# console.net
KiCad netlist of a schematic drawn in EAGLE
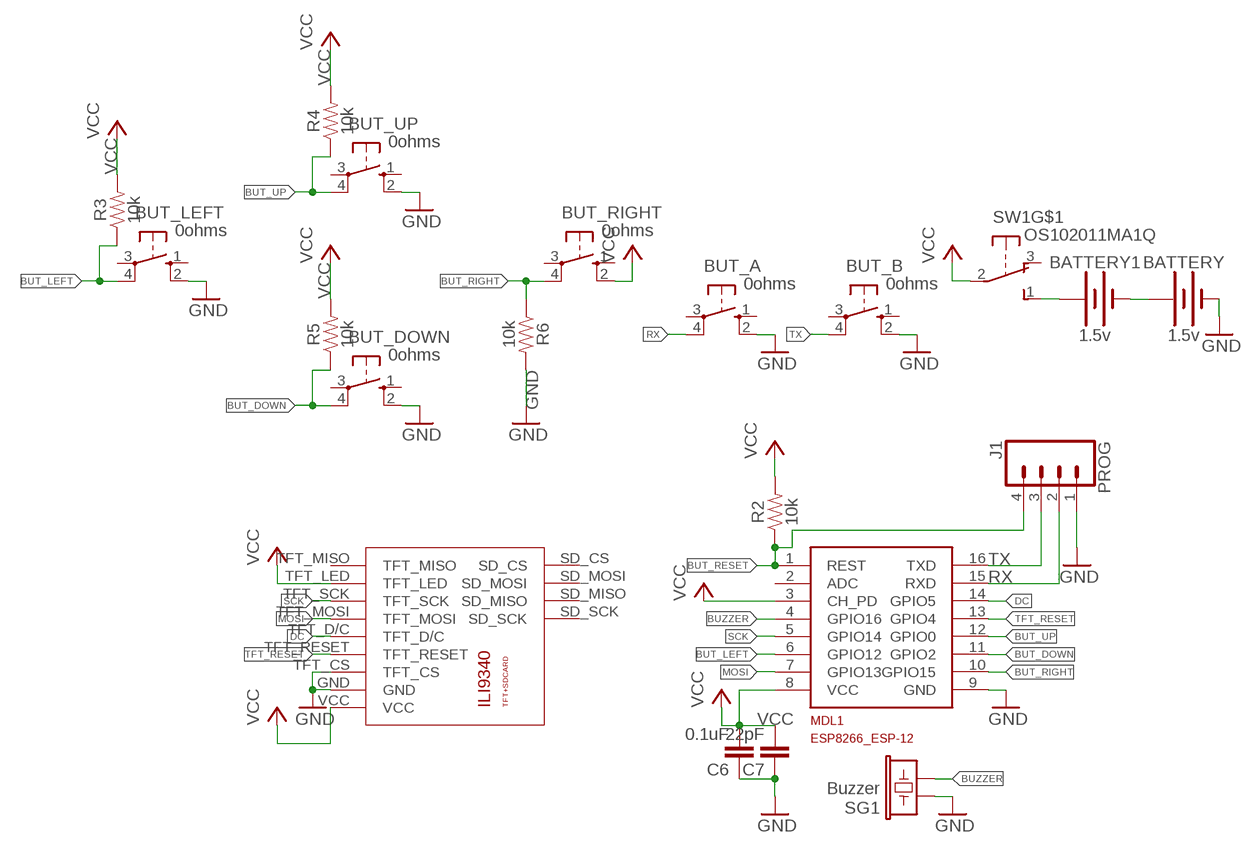
[diagram p0: schematic, sheet 1]

(export (version "E")
  (design (tool "Eeschema 10.0.6"))
  (components
    (comp (ref "BATTERY")
      (value "1.5v")
      (footprint "eagle-import:BATTERY-AA")
      (libsource (lib "eagle-import") (part "BATTERY-AA"))
    )
    (comp (ref "BATTERY1")
      (value "1.5v")
      (footprint "eagle-import:BATTERY-AA")
      (libsource (lib "eagle-import") (part "BATTERY-AA"))
    )
    (comp (ref "BUT_A")
      (value "0ohms")
      (footprint "eagle-import:B3F-10XX")
      (fields (field (name "MPN") "B3F-1000"))
      (libsource (lib "eagle-import") (part "10-XX"))
    )
    (comp (ref "BUT_B")
      (value "0ohms")
      (footprint "eagle-import:B3F-10XX")
      (fields (field (name "MPN") "B3F-1000"))
      (libsource (lib "eagle-import") (part "10-XX"))
    )
    (comp (ref "BUT_DOWN")
      (value "0ohms")
      (footprint "eagle-import:B3F-10XX")
      (fields (field (name "MPN") "B3F-1000"))
      (libsource (lib "eagle-import") (part "10-XX"))
    )
    (comp (ref "BUT_LEFT")
      (value "0ohms")
      (footprint "eagle-import:B3F-10XX")
      (fields (field (name "MPN") "B3F-1000"))
      (libsource (lib "eagle-import") (part "10-XX"))
    )
    (comp (ref "BUT_RIGHT")
      (value "0ohms")
      (footprint "eagle-import:B3F-10XX")
      (fields (field (name "MPN") "B3F-1000"))
      (libsource (lib "eagle-import") (part "10-XX"))
    )
    (comp (ref "BUT_UP")
      (value "0ohms")
      (footprint "eagle-import:B3F-10XX")
      (fields (field (name "MPN") "B3F-1000"))
      (libsource (lib "eagle-import") (part "10-XX"))
    )
    (comp (ref "C6")
      (value "0.1uF")
      (footprint "eagle-import:C0603")
      (libsource (lib "eagle-import") (part "C-EUC0603"))
    )
    (comp (ref "C7")
      (value "22pF")
      (footprint "eagle-import:C0603")
      (libsource (lib "eagle-import") (part "C-EUC0603"))
    )
    (comp (ref "J1")
      (value "PROG")
      (footprint "eagle-import:1X04_NO_SILK")
      (libsource (lib "eagle-import") (part "CONN_041X04_NO_SILK"))
    )
    (comp (ref "MDL1")
      (value "MCU")
      (footprint "eagle-import:ESP8266-ESP12")
      (libsource (lib "eagle-import") (part "ESP8266-12GPIO04/05_CORRECTED"))
    )
    (comp (ref "R2")
      (value "10k")
      (footprint "eagle-import:0603")
      (libsource (lib "eagle-import") (part "10KOHM-0603-1/10W-1%"))
    )
    (comp (ref "R3")
      (value "10k")
      (footprint "eagle-import:0603")
      (libsource (lib "eagle-import") (part "10KOHM-0603-1/10W-1%"))
    )
    (comp (ref "R4")
      (value "10k")
      (footprint "eagle-import:0603")
      (libsource (lib "eagle-import") (part "10KOHM-0603-1/10W-1%"))
    )
    (comp (ref "R5")
      (value "10k")
      (footprint "eagle-import:0603")
      (libsource (lib "eagle-import") (part "10KOHM-0603-1/10W-1%"))
    )
    (comp (ref "R6")
      (value "10k")
      (footprint "eagle-import:0603")
      (libsource (lib "eagle-import") (part "10KOHM-0603-1/10W-1%"))
    )
    (comp (ref "SG1")
      (value "Buzzer")
      (footprint "eagle-import:BUZZER-CCV")
      (libsource (lib "eagle-import") (part "BUZZERSMD2"))
    )
    (comp (ref "SW1")
      (value "OS102011MA1Q")
      (footprint "eagle-import:OS102011MA1Q")
      (libsource (lib "eagle-import") (part "OS102011MA1Q"))
    )
    (comp (ref "U$1")
      (value "ILI9340")
      (footprint "eagle-import:ILI9340")
      (libsource (lib "eagle-import") (part "ILI9340"))
    )
  )
  (nets
    (net (code "1") (name "BUT_DOWN") (class "Default")
      (node (ref "BUT_DOWN") (pin "4") (pinfunction "P1_4") (pintype "passive"))
      (node (ref "MDL1") (pin "11") (pinfunction "GPIO2_11") (pintype "bidirectional"))
      (node (ref "R5") (pin "1") (pinfunction "1_1") (pintype "passive"))
    )
    (net (code "2") (name "BUT_LEFT") (class "Default")
      (node (ref "BUT_LEFT") (pin "4") (pinfunction "P1_4") (pintype "passive"))
      (node (ref "MDL1") (pin "6") (pinfunction "GPIO12_6") (pintype "bidirectional"))
      (node (ref "R3") (pin "1") (pinfunction "1_1") (pintype "passive"))
    )
    (net (code "3") (name "BUT_RESET") (class "Default")
      (node (ref "J1") (pin "4") (pinfunction "4_4") (pintype "passive"))
      (node (ref "MDL1") (pin "1") (pinfunction "REST_1") (pintype "bidirectional"))
      (node (ref "R2") (pin "1") (pinfunction "1_1") (pintype "passive"))
    )
    (net (code "4") (name "BUT_RIGHT") (class "Default")
      (node (ref "BUT_RIGHT") (pin "4") (pinfunction "P1_4") (pintype "passive"))
      (node (ref "MDL1") (pin "10") (pinfunction "GPIO15_10") (pintype "bidirectional"))
      (node (ref "R6") (pin "1") (pinfunction "1_1") (pintype "passive"))
    )
    (net (code "5") (name "BUT_UP") (class "Default")
      (node (ref "BUT_UP") (pin "4") (pinfunction "P1_4") (pintype "passive"))
      (node (ref "MDL1") (pin "12") (pinfunction "GPIO0_12") (pintype "bidirectional"))
      (node (ref "R4") (pin "1") (pinfunction "1_1") (pintype "passive"))
    )
    (net (code "6") (name "BUZZER") (class "Default")
      (node (ref "MDL1") (pin "4") (pinfunction "GPIO16_4") (pintype "bidirectional"))
      (node (ref "SG1") (pin "-") (pinfunction "2_-") (pintype "passive"))
    )
    (net (code "7") (name "DC") (class "Default")
      (node (ref "MDL1") (pin "14") (pinfunction "GPIO5_14") (pintype "bidirectional"))
      (node (ref "U$1") (pin "TFT_D/C") (pinfunction "TFT_D/C_TFT_D/C") (pintype "input"))
    )
    (net (code "8") (name "GND") (class "Default")
      (node (ref "BATTERY") (pin "GND@1") (pinfunction "-_GND@1") (pintype "power_in"))
      (node (ref "BUT_A") (pin "2") (pinfunction "S1_2") (pintype "passive"))
      (node (ref "BUT_B") (pin "2") (pinfunction "S1_2") (pintype "passive"))
      (node (ref "BUT_DOWN") (pin "2") (pinfunction "S1_2") (pintype "passive"))
      (node (ref "BUT_LEFT") (pin "2") (pinfunction "S1_2") (pintype "passive"))
      (node (ref "BUT_UP") (pin "2") (pinfunction "S1_2") (pintype "passive"))
      (node (ref "C6") (pin "1") (pinfunction "1_1") (pintype "passive"))
      (node (ref "C7") (pin "1") (pinfunction "1_1") (pintype "passive"))
      (node (ref "J1") (pin "1") (pinfunction "1_1") (pintype "passive"))
      (node (ref "MDL1") (pin "9") (pinfunction "GND_9") (pintype "bidirectional"))
      (node (ref "R6") (pin "2") (pinfunction "2_2") (pintype "passive"))
      (node (ref "SG1") (pin "+") (pinfunction "1_+") (pintype "passive"))
      (node (ref "U$1") (pin "GND") (pinfunction "GND_GND") (pintype "power_in"))
      (node (ref "U$1") (pin "TFT_CS") (pinfunction "TFT_CS_TFT_CS") (pintype "input"))
    )
    (net (code "9") (name "MOSI") (class "Default")
      (node (ref "MDL1") (pin "7") (pinfunction "GPIO13_7") (pintype "bidirectional"))
      (node (ref "U$1") (pin "TFT_MOSI") (pinfunction "TFT_MOSI_TFT_MOSI") (pintype "input"))
    )
    (net (code "10") (name "Net-(BATTERY-+)") (class "Default")
      (node (ref "BATTERY") (pin "PWR@1") (pinfunction "+_PWR@1") (pintype "power_in"))
      (node (ref "BATTERY1") (pin "GND@1") (pinfunction "-_GND@1") (pintype "power_in"))
    )
    (net (code "11") (name "Net-(BATTERY1-+)") (class "Default")
      (node (ref "BATTERY1") (pin "PWR@1") (pinfunction "+_PWR@1") (pintype "power_in"))
      (node (ref "SW1") (pin "1") (pinfunction "S_1") (pintype "passive"))
    )
    (net (code "12") (name "RX") (class "Default")
      (node (ref "BUT_A") (pin "4") (pinfunction "P1_4") (pintype "passive"))
      (node (ref "J1") (pin "2") (pinfunction "2_2") (pintype "passive"))
      (node (ref "MDL1") (pin "15") (pinfunction "RXD_15") (pintype "bidirectional"))
    )
    (net (code "13") (name "SCK") (class "Default")
      (node (ref "MDL1") (pin "5") (pinfunction "GPIO14_5") (pintype "bidirectional"))
      (node (ref "U$1") (pin "TFT_SCK") (pinfunction "TFT_SCK_TFT_SCK") (pintype "input"))
    )
    (net (code "14") (name "TFT_RESET") (class "Default")
      (node (ref "MDL1") (pin "13") (pinfunction "GPIO4_13") (pintype "bidirectional"))
      (node (ref "U$1") (pin "TFT_RESET") (pinfunction "TFT_RESET_TFT_RESET") (pintype "input"))
    )
    (net (code "15") (name "TX") (class "Default")
      (node (ref "BUT_B") (pin "4") (pinfunction "P1_4") (pintype "passive"))
      (node (ref "J1") (pin "3") (pinfunction "3_3") (pintype "passive"))
      (node (ref "MDL1") (pin "16") (pinfunction "TXD_16") (pintype "bidirectional"))
    )
    (net (code "16") (name "VCC") (class "Default")
      (node (ref "BUT_RIGHT") (pin "2") (pinfunction "S1_2") (pintype "passive"))
      (node (ref "C6") (pin "2") (pinfunction "2_2") (pintype "passive"))
      (node (ref "C7") (pin "2") (pinfunction "2_2") (pintype "passive"))
      (node (ref "MDL1") (pin "3") (pinfunction "CH_PD_3") (pintype "bidirectional"))
      (node (ref "MDL1") (pin "8") (pinfunction "VCC_8") (pintype "bidirectional"))
      (node (ref "R2") (pin "2") (pinfunction "2_2") (pintype "passive"))
      (node (ref "R3") (pin "2") (pinfunction "2_2") (pintype "passive"))
      (node (ref "R4") (pin "2") (pinfunction "2_2") (pintype "passive"))
      (node (ref "R5") (pin "2") (pinfunction "2_2") (pintype "passive"))
      (node (ref "SW1") (pin "2") (pinfunction "P_2") (pintype "passive"))
      (node (ref "U$1") (pin "TFT_LED") (pinfunction "TFT_LED_TFT_LED") (pintype "power_in"))
      (node (ref "U$1") (pin "VCC") (pinfunction "VCC_VCC") (pintype "power_in"))
    )
    (net (code "17") (name "unconnected-(BUT_A-P-Pad3)") (class "Default")
      (node (ref "BUT_A") (pin "3") (pinfunction "P_3") (pintype "passive"))
    )
    (net (code "18") (name "unconnected-(BUT_A-S-Pad1)") (class "Default")
      (node (ref "BUT_A") (pin "1") (pinfunction "S_1") (pintype "passive"))
    )
    (net (code "19") (name "unconnected-(BUT_B-P-Pad3)") (class "Default")
      (node (ref "BUT_B") (pin "3") (pinfunction "P_3") (pintype "passive"))
    )
    (net (code "20") (name "unconnected-(BUT_B-S-Pad1)") (class "Default")
      (node (ref "BUT_B") (pin "1") (pinfunction "S_1") (pintype "passive"))
    )
    (net (code "21") (name "unconnected-(BUT_DOWN-P-Pad3)") (class "Default")
      (node (ref "BUT_DOWN") (pin "3") (pinfunction "P_3") (pintype "passive"))
    )
    (net (code "22") (name "unconnected-(BUT_DOWN-S-Pad1)") (class "Default")
      (node (ref "BUT_DOWN") (pin "1") (pinfunction "S_1") (pintype "passive"))
    )
    (net (code "23") (name "unconnected-(BUT_LEFT-P-Pad3)") (class "Default")
      (node (ref "BUT_LEFT") (pin "3") (pinfunction "P_3") (pintype "passive"))
    )
    (net (code "24") (name "unconnected-(BUT_LEFT-S-Pad1)") (class "Default")
      (node (ref "BUT_LEFT") (pin "1") (pinfunction "S_1") (pintype "passive"))
    )
    (net (code "25") (name "unconnected-(BUT_RIGHT-P-Pad3)") (class "Default")
      (node (ref "BUT_RIGHT") (pin "3") (pinfunction "P_3") (pintype "passive"))
    )
    (net (code "26") (name "unconnected-(BUT_RIGHT-S-Pad1)") (class "Default")
      (node (ref "BUT_RIGHT") (pin "1") (pinfunction "S_1") (pintype "passive"))
    )
    (net (code "27") (name "unconnected-(BUT_UP-P-Pad3)") (class "Default")
      (node (ref "BUT_UP") (pin "3") (pinfunction "P_3") (pintype "passive"))
    )
    (net (code "28") (name "unconnected-(BUT_UP-S-Pad1)") (class "Default")
      (node (ref "BUT_UP") (pin "1") (pinfunction "S_1") (pintype "passive"))
    )
    (net (code "29") (name "unconnected-(MDL1-ADC-Pad2)") (class "Default")
      (node (ref "MDL1") (pin "2") (pinfunction "ADC_2") (pintype "bidirectional"))
    )
    (net (code "30") (name "unconnected-(SW1A-O-Pad3)") (class "Default")
      (node (ref "SW1") (pin "3") (pinfunction "O_3") (pintype "passive"))
    )
    (net (code "31") (name "unconnected-(U$1-PadSD_CS)") (class "Default")
      (node (ref "U$1") (pin "SD_CS") (pinfunction "SD_CS_SD_CS") (pintype "input"))
    )
    (net (code "32") (name "unconnected-(U$1-PadSD_MISO)") (class "Default")
      (node (ref "U$1") (pin "SD_MISO") (pinfunction "SD_MISO_SD_MISO") (pintype "output"))
    )
    (net (code "33") (name "unconnected-(U$1-PadSD_MOSI)") (class "Default")
      (node (ref "U$1") (pin "SD_MOSI") (pinfunction "SD_MOSI_SD_MOSI") (pintype "input"))
    )
    (net (code "34") (name "unconnected-(U$1-PadSD_SCK)") (class "Default")
      (node (ref "U$1") (pin "SD_SCK") (pinfunction "SD_SCK_SD_SCK") (pintype "input"))
    )
    (net (code "35") (name "unconnected-(U$1-PadTFT_MISO)") (class "Default")
      (node (ref "U$1") (pin "TFT_MISO") (pinfunction "TFT_MISO_TFT_MISO") (pintype "no_connect"))
    )
  )
)
